# NYSERDA_LCS_PROJECT_V1.net
KiCad netlist of a schematic drawn in EAGLE
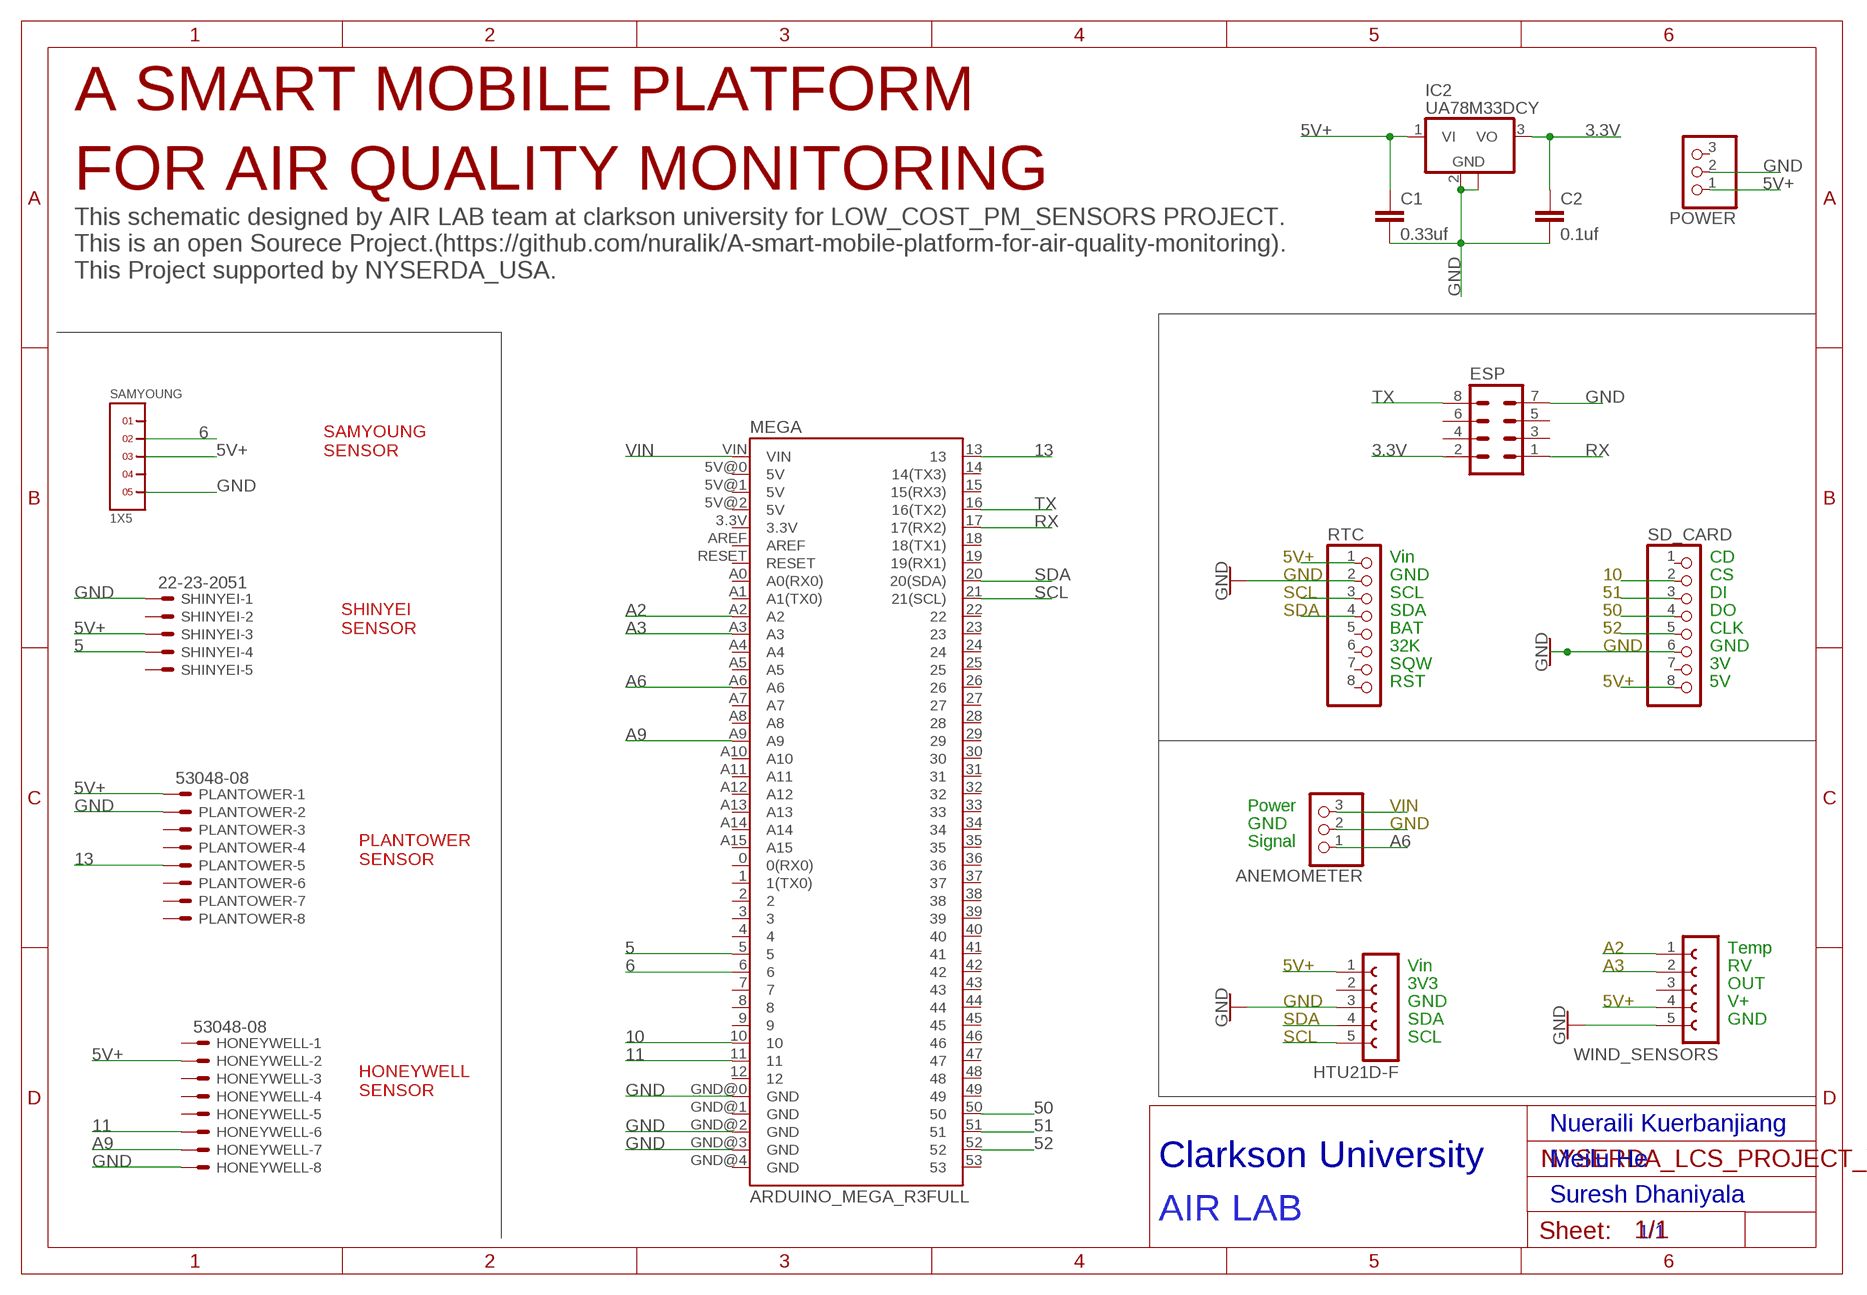
[diagram p0: schematic, sheet 1]

(export (version "E")
  (design (tool "Eeschema 10.0.6"))
  (components
    (comp (ref "ANEMOMETER")
      (value "PINHD-1X3")
      (footprint "eagle-import:1X03")
      (libsource (lib "eagle-import") (part "PINHD-1X3"))
    )
    (comp (ref "C1")
      (value "0.33uf")
      (footprint "eagle-import:C2.5-2")
      (libsource (lib "eagle-import") (part "C2.5/2"))
    )
    (comp (ref "C2")
      (value "0.1uf")
      (footprint "eagle-import:C2.5-2")
      (libsource (lib "eagle-import") (part "C2.5/2"))
    )
    (comp (ref "ESP")
      (value "MA04-2")
      (footprint "eagle-import:MA04-2")
      (libsource (lib "eagle-import") (part "MA04-2"))
    )
    (comp (ref "HONEYWELL")
      (value "53048-08")
      (footprint "eagle-import:53048-08")
      (fields (field (name "MF") "WALDOM/MOLEX") (field (name "MPN") "53048-0810"))
      (libsource (lib "eagle-import") (part "53?-08048"))
    )
    (comp (ref "HTU21D-F")
      (value "FE05-1")
      (footprint "eagle-import:FE05-1")
      (libsource (lib "eagle-import") (part "FE05-1"))
    )
    (comp (ref "IC2")
      (value "UA78M33DCY")
      (footprint "eagle-import:SOT223")
      (libsource (lib "eagle-import") (part "UA78MDCY33"))
    )
    (comp (ref "MEGA")
      (value "ARDUINO_MEGA_R3FULL")
      (footprint "eagle-import:ARDUINO_MEGA")
      (libsource (lib "eagle-import") (part "ARDUINO_MEGA_R3FULL"))
    )
    (comp (ref "PLANTOWER")
      (value "53048-08")
      (footprint "eagle-import:53048-08")
      (fields (field (name "MF") "WALDOM/MOLEX") (field (name "MPN") "53048-0810"))
      (libsource (lib "eagle-import") (part "53?-08048"))
    )
    (comp (ref "POWER")
      (value "PINHD-1X3")
      (footprint "eagle-import:1X03")
      (libsource (lib "eagle-import") (part "PINHD-1X3"))
    )
    (comp (ref "RTC")
      (value "PINHD-1X8BIG")
      (footprint "eagle-import:1X08-BIG")
      (libsource (lib "eagle-import") (part "PINHD-1X8BIG"))
    )
    (comp (ref "SAMYOUNG")
      (value "1X5")
      (footprint "eagle-import:1X5")
      (libsource (lib "eagle-import") (part "1X5"))
    )
    (comp (ref "SD_CARD")
      (value "PINHD-1X8BIG")
      (footprint "eagle-import:1X08-BIG")
      (libsource (lib "eagle-import") (part "PINHD-1X8BIG"))
    )
    (comp (ref "SHINYEI")
      (value "22-23-2051")
      (footprint "eagle-import:22-23-2051")
      (fields (field (name "MF") "MOLEX"))
      (libsource (lib "eagle-import") (part "22-23-2051"))
    )
    (comp (ref "WIND_SENSORS")
      (value "FE05-1")
      (footprint "eagle-import:FE05-1")
      (libsource (lib "eagle-import") (part "FE05-1"))
    )
  )
  (nets
    (net (code "1") (name "/3.3V") (class "Default")
      (node (ref "C2") (pin "1") (pinfunction "1_1") (pintype "passive"))
      (node (ref "ESP") (pin "2") (pinfunction "2_2") (pintype "passive"))
      (node (ref "IC2") (pin "3") (pinfunction "VO_3") (pintype "passive"))
    )
    (net (code "2") (name "/5") (class "Default")
      (node (ref "MEGA") (pin "5") (pinfunction "5_5") (pintype "bidirectional"))
      (node (ref "SHINYEI") (pin "4") (pinfunction "S_4") (pintype "passive"))
    )
    (net (code "3") (name "/5V+") (class "Default")
      (node (ref "C1") (pin "1") (pinfunction "1_1") (pintype "passive"))
      (node (ref "HONEYWELL") (pin "2") (pinfunction "S_2") (pintype "passive"))
      (node (ref "HTU21D-F") (pin "1") (pinfunction "1_1") (pintype "passive"))
      (node (ref "IC2") (pin "1") (pinfunction "VI_1") (pintype "input"))
      (node (ref "PLANTOWER") (pin "1") (pinfunction "S_1") (pintype "passive"))
      (node (ref "POWER") (pin "1") (pinfunction "1_1") (pintype "passive"))
      (node (ref "RTC") (pin "1") (pinfunction "1_1") (pintype "passive"))
      (node (ref "SAMYOUNG") (pin "3") (pinfunction "3_3") (pintype "bidirectional"))
      (node (ref "SD_CARD") (pin "8") (pinfunction "8_8") (pintype "passive"))
      (node (ref "SHINYEI") (pin "3") (pinfunction "S_3") (pintype "passive"))
      (node (ref "WIND_SENSORS") (pin "4") (pinfunction "4_4") (pintype "passive"))
    )
    (net (code "4") (name "/6") (class "Default")
      (node (ref "MEGA") (pin "6") (pinfunction "6_6") (pintype "bidirectional"))
      (node (ref "SAMYOUNG") (pin "2") (pinfunction "2_2") (pintype "bidirectional"))
    )
    (net (code "5") (name "/10") (class "Default")
      (node (ref "MEGA") (pin "10") (pinfunction "10_10") (pintype "bidirectional"))
      (node (ref "SD_CARD") (pin "2") (pinfunction "2_2") (pintype "passive"))
    )
    (net (code "6") (name "/11") (class "Default")
      (node (ref "HONEYWELL") (pin "6") (pinfunction "S_6") (pintype "passive"))
      (node (ref "MEGA") (pin "11") (pinfunction "11_11") (pintype "bidirectional"))
    )
    (net (code "7") (name "/13") (class "Default")
      (node (ref "MEGA") (pin "13") (pinfunction "13_13") (pintype "bidirectional"))
      (node (ref "PLANTOWER") (pin "5") (pinfunction "S_5") (pintype "passive"))
    )
    (net (code "8") (name "/50") (class "Default")
      (node (ref "MEGA") (pin "50") (pinfunction "50_50") (pintype "bidirectional"))
      (node (ref "SD_CARD") (pin "4") (pinfunction "4_4") (pintype "passive"))
    )
    (net (code "9") (name "/51") (class "Default")
      (node (ref "MEGA") (pin "51") (pinfunction "51_51") (pintype "bidirectional"))
      (node (ref "SD_CARD") (pin "3") (pinfunction "3_3") (pintype "passive"))
    )
    (net (code "10") (name "/52") (class "Default")
      (node (ref "MEGA") (pin "52") (pinfunction "52_52") (pintype "bidirectional"))
      (node (ref "SD_CARD") (pin "5") (pinfunction "5_5") (pintype "passive"))
    )
    (net (code "11") (name "/A2") (class "Default")
      (node (ref "MEGA") (pin "A2") (pinfunction "A2_A2") (pintype "bidirectional"))
      (node (ref "WIND_SENSORS") (pin "1") (pinfunction "1_1") (pintype "passive"))
    )
    (net (code "12") (name "/A3") (class "Default")
      (node (ref "MEGA") (pin "A3") (pinfunction "A3_A3") (pintype "bidirectional"))
      (node (ref "WIND_SENSORS") (pin "2") (pinfunction "2_2") (pintype "passive"))
    )
    (net (code "13") (name "/A6") (class "Default")
      (node (ref "ANEMOMETER") (pin "1") (pinfunction "1_1") (pintype "passive"))
      (node (ref "MEGA") (pin "A6") (pinfunction "A6_A6") (pintype "bidirectional"))
    )
    (net (code "14") (name "/A9") (class "Default")
      (node (ref "HONEYWELL") (pin "7") (pinfunction "S_7") (pintype "passive"))
      (node (ref "MEGA") (pin "A9") (pinfunction "A9_A9") (pintype "bidirectional"))
    )
    (net (code "15") (name "/RX") (class "Default")
      (node (ref "ESP") (pin "1") (pinfunction "1_1") (pintype "passive"))
      (node (ref "MEGA") (pin "17") (pinfunction "17(RX2)_17") (pintype "bidirectional"))
    )
    (net (code "16") (name "/SCL") (class "Default")
      (node (ref "HTU21D-F") (pin "5") (pinfunction "5_5") (pintype "passive"))
      (node (ref "MEGA") (pin "21") (pinfunction "21(SCL)_21") (pintype "bidirectional"))
      (node (ref "RTC") (pin "3") (pinfunction "3_3") (pintype "passive"))
    )
    (net (code "17") (name "/SDA") (class "Default")
      (node (ref "HTU21D-F") (pin "4") (pinfunction "4_4") (pintype "passive"))
      (node (ref "MEGA") (pin "20") (pinfunction "20(SDA)_20") (pintype "bidirectional"))
      (node (ref "RTC") (pin "4") (pinfunction "4_4") (pintype "passive"))
    )
    (net (code "18") (name "/TX") (class "Default")
      (node (ref "ESP") (pin "8") (pinfunction "8_8") (pintype "passive"))
      (node (ref "MEGA") (pin "16") (pinfunction "16(TX2)_16") (pintype "bidirectional"))
    )
    (net (code "19") (name "/VIN") (class "Default")
      (node (ref "ANEMOMETER") (pin "3") (pinfunction "3_3") (pintype "passive"))
      (node (ref "MEGA") (pin "VIN") (pinfunction "VIN_VIN") (pintype "bidirectional"))
    )
    (net (code "20") (name "GND") (class "Default")
      (node (ref "ANEMOMETER") (pin "2") (pinfunction "2_2") (pintype "passive"))
      (node (ref "C1") (pin "2") (pinfunction "2_2") (pintype "passive"))
      (node (ref "C2") (pin "2") (pinfunction "2_2") (pintype "passive"))
      (node (ref "ESP") (pin "7") (pinfunction "7_7") (pintype "passive"))
      (node (ref "HONEYWELL") (pin "8") (pinfunction "S_8") (pintype "passive"))
      (node (ref "HTU21D-F") (pin "3") (pinfunction "3_3") (pintype "passive"))
      (node (ref "IC2") (pin "2") (pinfunction "GND_2") (pintype "passive"))
      (node (ref "IC2") (pin "4") (pinfunction "GND_4") (pintype "passive"))
      (node (ref "MEGA") (pin "GND@0") (pinfunction "GND_GND@0") (pintype "bidirectional"))
      (node (ref "MEGA") (pin "GND@2") (pinfunction "GND_GND@2") (pintype "bidirectional"))
      (node (ref "MEGA") (pin "GND@3") (pinfunction "GND_GND@3") (pintype "bidirectional"))
      (node (ref "PLANTOWER") (pin "2") (pinfunction "S_2") (pintype "passive"))
      (node (ref "POWER") (pin "2") (pinfunction "2_2") (pintype "passive"))
      (node (ref "RTC") (pin "2") (pinfunction "2_2") (pintype "passive"))
      (node (ref "SAMYOUNG") (pin "5") (pinfunction "5_5") (pintype "bidirectional"))
      (node (ref "SD_CARD") (pin "6") (pinfunction "6_6") (pintype "passive"))
      (node (ref "SHINYEI") (pin "1") (pinfunction "S_1") (pintype "passive"))
      (node (ref "WIND_SENSORS") (pin "5") (pinfunction "5_5") (pintype "passive"))
    )
    (net (code "21") (name "unconnected-(ESP-Pad3)") (class "Default")
      (node (ref "ESP") (pin "3") (pinfunction "3_3") (pintype "passive"))
    )
    (net (code "22") (name "unconnected-(ESP-Pad4)") (class "Default")
      (node (ref "ESP") (pin "4") (pinfunction "4_4") (pintype "passive"))
    )
    (net (code "23") (name "unconnected-(ESP-Pad5)") (class "Default")
      (node (ref "ESP") (pin "5") (pinfunction "5_5") (pintype "passive"))
    )
    (net (code "24") (name "unconnected-(ESP-Pad6)") (class "Default")
      (node (ref "ESP") (pin "6") (pinfunction "6_6") (pintype "passive"))
    )
    (net (code "25") (name "unconnected-(HONEYWELLA-S-Pad1)") (class "Default")
      (node (ref "HONEYWELL") (pin "1") (pinfunction "S_1") (pintype "passive"))
    )
    (net (code "26") (name "unconnected-(HONEYWELLC-S-Pad3)") (class "Default")
      (node (ref "HONEYWELL") (pin "3") (pinfunction "S_3") (pintype "passive"))
    )
    (net (code "27") (name "unconnected-(HONEYWELLD-S-Pad4)") (class "Default")
      (node (ref "HONEYWELL") (pin "4") (pinfunction "S_4") (pintype "passive"))
    )
    (net (code "28") (name "unconnected-(HONEYWELLE-S-Pad5)") (class "Default")
      (node (ref "HONEYWELL") (pin "5") (pinfunction "S_5") (pintype "passive"))
    )
    (net (code "29") (name "unconnected-(HTU21D-F-Pad2)") (class "Default")
      (node (ref "HTU21D-F") (pin "2") (pinfunction "2_2") (pintype "passive"))
    )
    (net (code "30") (name "unconnected-(MEGA-0(RX0)-Pad0)") (class "Default")
      (node (ref "MEGA") (pin "0") (pinfunction "0(RX0)_0") (pintype "bidirectional"))
    )
    (net (code "31") (name "unconnected-(MEGA-1(TX0)-Pad1)") (class "Default")
      (node (ref "MEGA") (pin "1") (pinfunction "1(TX0)_1") (pintype "bidirectional"))
    )
    (net (code "32") (name "unconnected-(MEGA-5V-Pad5V@0)") (class "Default")
      (node (ref "MEGA") (pin "5V@0") (pinfunction "5V_5V@0") (pintype "bidirectional"))
    )
    (net (code "33") (name "unconnected-(MEGA-5V-Pad5V@1)") (class "Default")
      (node (ref "MEGA") (pin "5V@1") (pinfunction "5V_5V@1") (pintype "bidirectional"))
    )
    (net (code "34") (name "unconnected-(MEGA-5V-Pad5V@2)") (class "Default")
      (node (ref "MEGA") (pin "5V@2") (pinfunction "5V_5V@2") (pintype "bidirectional"))
    )
    (net (code "35") (name "unconnected-(MEGA-14(TX3)-Pad14)") (class "Default")
      (node (ref "MEGA") (pin "14") (pinfunction "14(TX3)_14") (pintype "bidirectional"))
    )
    (net (code "36") (name "unconnected-(MEGA-15(RX3)-Pad15)") (class "Default")
      (node (ref "MEGA") (pin "15") (pinfunction "15(RX3)_15") (pintype "bidirectional"))
    )
    (net (code "37") (name "unconnected-(MEGA-18(TX1)-Pad18)") (class "Default")
      (node (ref "MEGA") (pin "18") (pinfunction "18(TX1)_18") (pintype "bidirectional"))
    )
    (net (code "38") (name "unconnected-(MEGA-19(RX1)-Pad19)") (class "Default")
      (node (ref "MEGA") (pin "19") (pinfunction "19(RX1)_19") (pintype "bidirectional"))
    )
    (net (code "39") (name "unconnected-(MEGA-A0(RX0)-PadA0)") (class "Default")
      (node (ref "MEGA") (pin "A0") (pinfunction "A0(RX0)_A0") (pintype "bidirectional"))
    )
    (net (code "40") (name "unconnected-(MEGA-A1(TX0)-PadA1)") (class "Default")
      (node (ref "MEGA") (pin "A1") (pinfunction "A1(TX0)_A1") (pintype "bidirectional"))
    )
    (net (code "41") (name "unconnected-(MEGA-GND-PadGND@1)") (class "Default")
      (node (ref "MEGA") (pin "GND@1") (pinfunction "GND_GND@1") (pintype "bidirectional"))
    )
    (net (code "42") (name "unconnected-(MEGA-GND-PadGND@4)") (class "Default")
      (node (ref "MEGA") (pin "GND@4") (pinfunction "GND_GND@4") (pintype "bidirectional"))
    )
    (net (code "43") (name "unconnected-(MEGA-Pad2)") (class "Default")
      (node (ref "MEGA") (pin "2") (pinfunction "2_2") (pintype "bidirectional"))
    )
    (net (code "44") (name "unconnected-(MEGA-Pad3)") (class "Default")
      (node (ref "MEGA") (pin "3") (pinfunction "3_3") (pintype "bidirectional"))
    )
    (net (code "45") (name "unconnected-(MEGA-Pad3.3V)") (class "Default")
      (node (ref "MEGA") (pin "3.3V") (pinfunction "3.3V_3.3V") (pintype "bidirectional"))
    )
    (net (code "46") (name "unconnected-(MEGA-Pad4)") (class "Default")
      (node (ref "MEGA") (pin "4") (pinfunction "4_4") (pintype "bidirectional"))
    )
    (net (code "47") (name "unconnected-(MEGA-Pad7)") (class "Default")
      (node (ref "MEGA") (pin "7") (pinfunction "7_7") (pintype "bidirectional"))
    )
    (net (code "48") (name "unconnected-(MEGA-Pad8)") (class "Default")
      (node (ref "MEGA") (pin "8") (pinfunction "8_8") (pintype "bidirectional"))
    )
    (net (code "49") (name "unconnected-(MEGA-Pad9)") (class "Default")
      (node (ref "MEGA") (pin "9") (pinfunction "9_9") (pintype "bidirectional"))
    )
    (net (code "50") (name "unconnected-(MEGA-Pad12)") (class "Default")
      (node (ref "MEGA") (pin "12") (pinfunction "12_12") (pintype "bidirectional"))
    )
    (net (code "51") (name "unconnected-(MEGA-Pad22)") (class "Default")
      (node (ref "MEGA") (pin "22") (pinfunction "22_22") (pintype "bidirectional"))
    )
    (net (code "52") (name "unconnected-(MEGA-Pad23)") (class "Default")
      (node (ref "MEGA") (pin "23") (pinfunction "23_23") (pintype "bidirectional"))
    )
    (net (code "53") (name "unconnected-(MEGA-Pad24)") (class "Default")
      (node (ref "MEGA") (pin "24") (pinfunction "24_24") (pintype "bidirectional"))
    )
    (net (code "54") (name "unconnected-(MEGA-Pad25)") (class "Default")
      (node (ref "MEGA") (pin "25") (pinfunction "25_25") (pintype "bidirectional"))
    )
    (net (code "55") (name "unconnected-(MEGA-Pad26)") (class "Default")
      (node (ref "MEGA") (pin "26") (pinfunction "26_26") (pintype "bidirectional"))
    )
    (net (code "56") (name "unconnected-(MEGA-Pad27)") (class "Default")
      (node (ref "MEGA") (pin "27") (pinfunction "27_27") (pintype "bidirectional"))
    )
    (net (code "57") (name "unconnected-(MEGA-Pad28)") (class "Default")
      (node (ref "MEGA") (pin "28") (pinfunction "28_28") (pintype "bidirectional"))
    )
    (net (code "58") (name "unconnected-(MEGA-Pad29)") (class "Default")
      (node (ref "MEGA") (pin "29") (pinfunction "29_29") (pintype "bidirectional"))
    )
    (net (code "59") (name "unconnected-(MEGA-Pad30)") (class "Default")
      (node (ref "MEGA") (pin "30") (pinfunction "30_30") (pintype "bidirectional"))
    )
    (net (code "60") (name "unconnected-(MEGA-Pad31)") (class "Default")
      (node (ref "MEGA") (pin "31") (pinfunction "31_31") (pintype "bidirectional"))
    )
    (net (code "61") (name "unconnected-(MEGA-Pad32)") (class "Default")
      (node (ref "MEGA") (pin "32") (pinfunction "32_32") (pintype "bidirectional"))
    )
    (net (code "62") (name "unconnected-(MEGA-Pad33)") (class "Default")
      (node (ref "MEGA") (pin "33") (pinfunction "33_33") (pintype "bidirectional"))
    )
    (net (code "63") (name "unconnected-(MEGA-Pad34)") (class "Default")
      (node (ref "MEGA") (pin "34") (pinfunction "34_34") (pintype "bidirectional"))
    )
    (net (code "64") (name "unconnected-(MEGA-Pad35)") (class "Default")
      (node (ref "MEGA") (pin "35") (pinfunction "35_35") (pintype "bidirectional"))
    )
    (net (code "65") (name "unconnected-(MEGA-Pad36)") (class "Default")
      (node (ref "MEGA") (pin "36") (pinfunction "36_36") (pintype "bidirectional"))
    )
    (net (code "66") (name "unconnected-(MEGA-Pad37)") (class "Default")
      (node (ref "MEGA") (pin "37") (pinfunction "37_37") (pintype "bidirectional"))
    )
    (net (code "67") (name "unconnected-(MEGA-Pad38)") (class "Default")
      (node (ref "MEGA") (pin "38") (pinfunction "38_38") (pintype "bidirectional"))
    )
    (net (code "68") (name "unconnected-(MEGA-Pad39)") (class "Default")
      (node (ref "MEGA") (pin "39") (pinfunction "39_39") (pintype "bidirectional"))
    )
    (net (code "69") (name "unconnected-(MEGA-Pad40)") (class "Default")
      (node (ref "MEGA") (pin "40") (pinfunction "40_40") (pintype "bidirectional"))
    )
    (net (code "70") (name "unconnected-(MEGA-Pad41)") (class "Default")
      (node (ref "MEGA") (pin "41") (pinfunction "41_41") (pintype "bidirectional"))
    )
    (net (code "71") (name "unconnected-(MEGA-Pad42)") (class "Default")
      (node (ref "MEGA") (pin "42") (pinfunction "42_42") (pintype "bidirectional"))
    )
    (net (code "72") (name "unconnected-(MEGA-Pad43)") (class "Default")
      (node (ref "MEGA") (pin "43") (pinfunction "43_43") (pintype "bidirectional"))
    )
    (net (code "73") (name "unconnected-(MEGA-Pad44)") (class "Default")
      (node (ref "MEGA") (pin "44") (pinfunction "44_44") (pintype "bidirectional"))
    )
    (net (code "74") (name "unconnected-(MEGA-Pad45)") (class "Default")
      (node (ref "MEGA") (pin "45") (pinfunction "45_45") (pintype "bidirectional"))
    )
    (net (code "75") (name "unconnected-(MEGA-Pad46)") (class "Default")
      (node (ref "MEGA") (pin "46") (pinfunction "46_46") (pintype "bidirectional"))
    )
    (net (code "76") (name "unconnected-(MEGA-Pad47)") (class "Default")
      (node (ref "MEGA") (pin "47") (pinfunction "47_47") (pintype "bidirectional"))
    )
    (net (code "77") (name "unconnected-(MEGA-Pad48)") (class "Default")
      (node (ref "MEGA") (pin "48") (pinfunction "48_48") (pintype "bidirectional"))
    )
    (net (code "78") (name "unconnected-(MEGA-Pad49)") (class "Default")
      (node (ref "MEGA") (pin "49") (pinfunction "49_49") (pintype "bidirectional"))
    )
    (net (code "79") (name "unconnected-(MEGA-Pad53)") (class "Default")
      (node (ref "MEGA") (pin "53") (pinfunction "53_53") (pintype "bidirectional"))
    )
    (net (code "80") (name "unconnected-(MEGA-PadA4)") (class "Default")
      (node (ref "MEGA") (pin "A4") (pinfunction "A4_A4") (pintype "bidirectional"))
    )
    (net (code "81") (name "unconnected-(MEGA-PadA5)") (class "Default")
      (node (ref "MEGA") (pin "A5") (pinfunction "A5_A5") (pintype "bidirectional"))
    )
    (net (code "82") (name "unconnected-(MEGA-PadA7)") (class "Default")
      (node (ref "MEGA") (pin "A7") (pinfunction "A7_A7") (pintype "bidirectional"))
    )
    (net (code "83") (name "unconnected-(MEGA-PadA8)") (class "Default")
      (node (ref "MEGA") (pin "A8") (pinfunction "A8_A8") (pintype "bidirectional"))
    )
    (net (code "84") (name "unconnected-(MEGA-PadA10)") (class "Default")
      (node (ref "MEGA") (pin "A10") (pinfunction "A10_A10") (pintype "bidirectional"))
    )
    (net (code "85") (name "unconnected-(MEGA-PadA11)") (class "Default")
      (node (ref "MEGA") (pin "A11") (pinfunction "A11_A11") (pintype "bidirectional"))
    )
    (net (code "86") (name "unconnected-(MEGA-PadA12)") (class "Default")
      (node (ref "MEGA") (pin "A12") (pinfunction "A12_A12") (pintype "bidirectional"))
    )
    (net (code "87") (name "unconnected-(MEGA-PadA13)") (class "Default")
      (node (ref "MEGA") (pin "A13") (pinfunction "A13_A13") (pintype "bidirectional"))
    )
    (net (code "88") (name "unconnected-(MEGA-PadA14)") (class "Default")
      (node (ref "MEGA") (pin "A14") (pinfunction "A14_A14") (pintype "bidirectional"))
    )
    (net (code "89") (name "unconnected-(MEGA-PadA15)") (class "Default")
      (node (ref "MEGA") (pin "A15") (pinfunction "A15_A15") (pintype "bidirectional"))
    )
    (net (code "90") (name "unconnected-(MEGA-PadAREF)") (class "Default")
      (node (ref "MEGA") (pin "AREF") (pinfunction "AREF_AREF") (pintype "bidirectional"))
    )
    (net (code "91") (name "unconnected-(MEGA-PadRESET)") (class "Default")
      (node (ref "MEGA") (pin "RESET") (pinfunction "RESET_RESET") (pintype "bidirectional"))
    )
    (net (code "92") (name "unconnected-(PLANTOWERC-S-Pad3)") (class "Default")
      (node (ref "PLANTOWER") (pin "3") (pinfunction "S_3") (pintype "passive"))
    )
    (net (code "93") (name "unconnected-(PLANTOWERD-S-Pad4)") (class "Default")
      (node (ref "PLANTOWER") (pin "4") (pinfunction "S_4") (pintype "passive"))
    )
    (net (code "94") (name "unconnected-(PLANTOWERF-S-Pad6)") (class "Default")
      (node (ref "PLANTOWER") (pin "6") (pinfunction "S_6") (pintype "passive"))
    )
    (net (code "95") (name "unconnected-(PLANTOWERG-S-Pad7)") (class "Default")
      (node (ref "PLANTOWER") (pin "7") (pinfunction "S_7") (pintype "passive"))
    )
    (net (code "96") (name "unconnected-(PLANTOWERH-S-Pad8)") (class "Default")
      (node (ref "PLANTOWER") (pin "8") (pinfunction "S_8") (pintype "passive"))
    )
    (net (code "97") (name "unconnected-(POWER-Pad3)") (class "Default")
      (node (ref "POWER") (pin "3") (pinfunction "3_3") (pintype "passive"))
    )
    (net (code "98") (name "unconnected-(RTC-Pad5)") (class "Default")
      (node (ref "RTC") (pin "5") (pinfunction "5_5") (pintype "passive"))
    )
    (net (code "99") (name "unconnected-(RTC-Pad6)") (class "Default")
      (node (ref "RTC") (pin "6") (pinfunction "6_6") (pintype "passive"))
    )
    (net (code "100") (name "unconnected-(RTC-Pad7)") (class "Default")
      (node (ref "RTC") (pin "7") (pinfunction "7_7") (pintype "passive"))
    )
    (net (code "101") (name "unconnected-(RTC-Pad8)") (class "Default")
      (node (ref "RTC") (pin "8") (pinfunction "8_8") (pintype "passive"))
    )
    (net (code "102") (name "unconnected-(SAMYOUNG-Pad1)") (class "Default")
      (node (ref "SAMYOUNG") (pin "1") (pinfunction "1_1") (pintype "bidirectional"))
    )
    (net (code "103") (name "unconnected-(SAMYOUNG-Pad4)") (class "Default")
      (node (ref "SAMYOUNG") (pin "4") (pinfunction "4_4") (pintype "bidirectional"))
    )
    (net (code "104") (name "unconnected-(SD_CARD-Pad1)") (class "Default")
      (node (ref "SD_CARD") (pin "1") (pinfunction "1_1") (pintype "passive"))
    )
    (net (code "105") (name "unconnected-(SD_CARD-Pad7)") (class "Default")
      (node (ref "SD_CARD") (pin "7") (pinfunction "7_7") (pintype "passive"))
    )
    (net (code "106") (name "unconnected-(SHINYEIB-S-Pad2)") (class "Default")
      (node (ref "SHINYEI") (pin "2") (pinfunction "S_2") (pintype "passive"))
    )
    (net (code "107") (name "unconnected-(SHINYEIE-S-Pad5)") (class "Default")
      (node (ref "SHINYEI") (pin "5") (pinfunction "S_5") (pintype "passive"))
    )
    (net (code "108") (name "unconnected-(WIND_SENSORS-Pad3)") (class "Default")
      (node (ref "WIND_SENSORS") (pin "3") (pinfunction "3_3") (pintype "passive"))
    )
  )
)
